# prototype1-ftdi-as-breakout.net
KiCad netlist of a schematic drawn in EAGLE
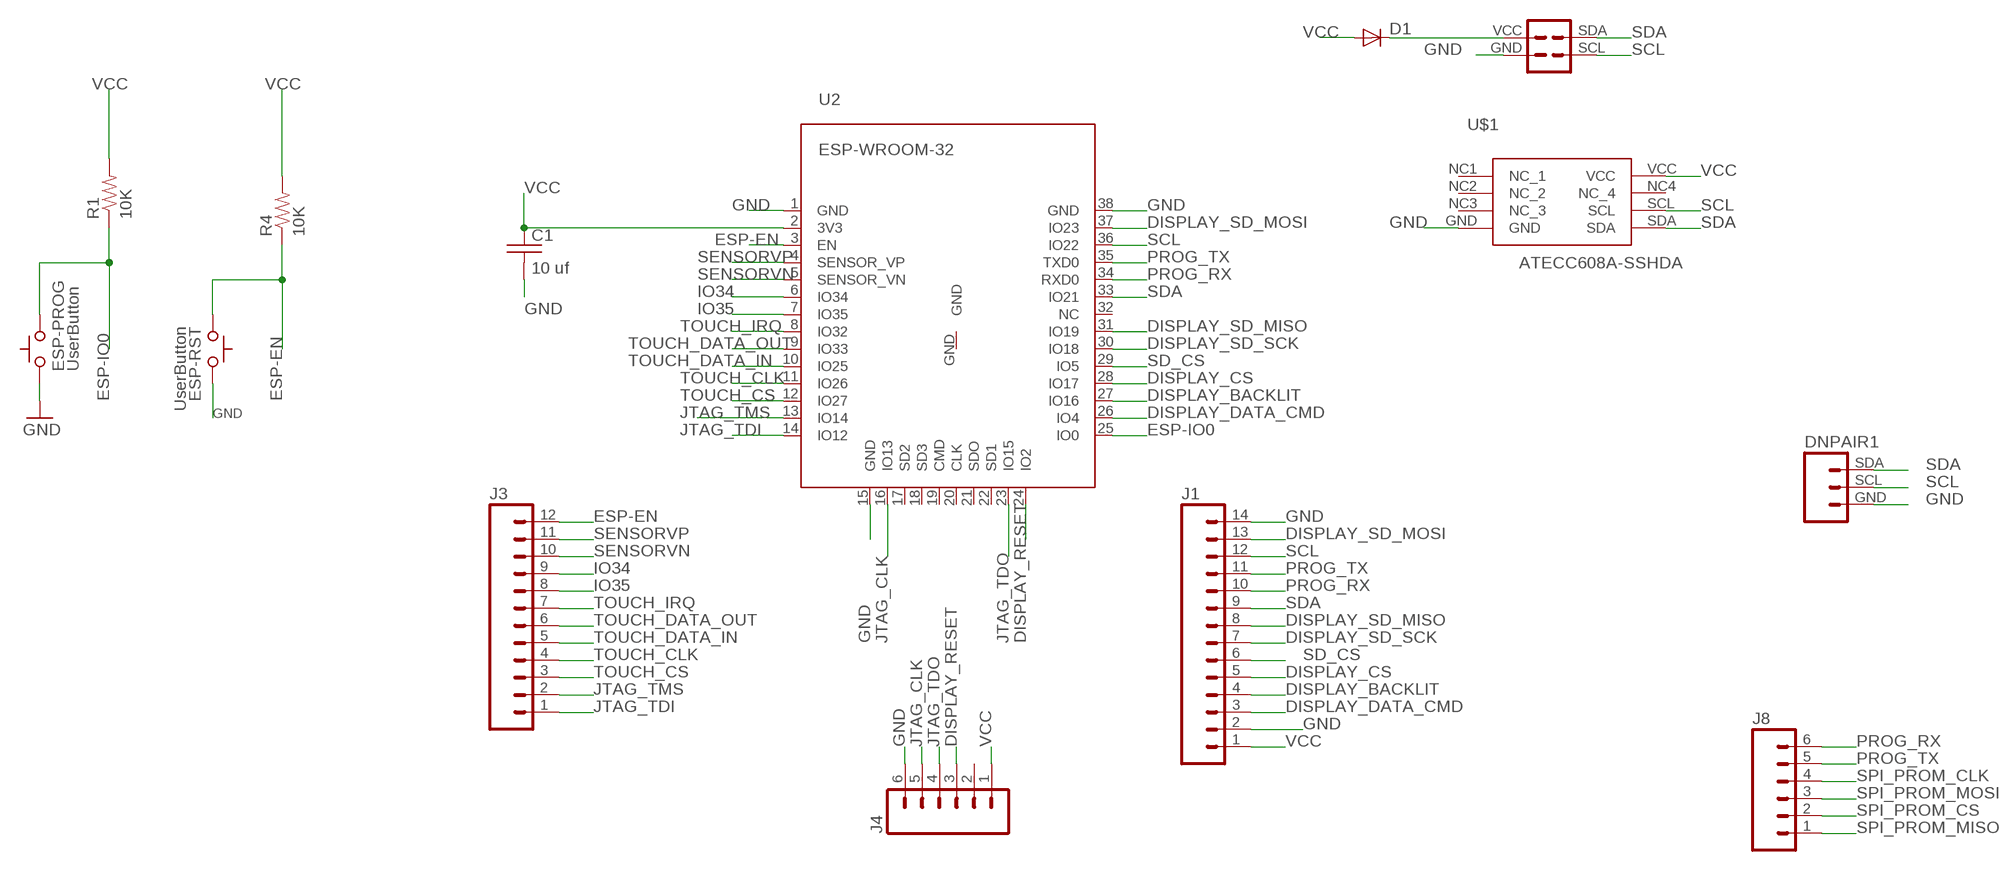
[diagram p0: schematic, sheet 1]
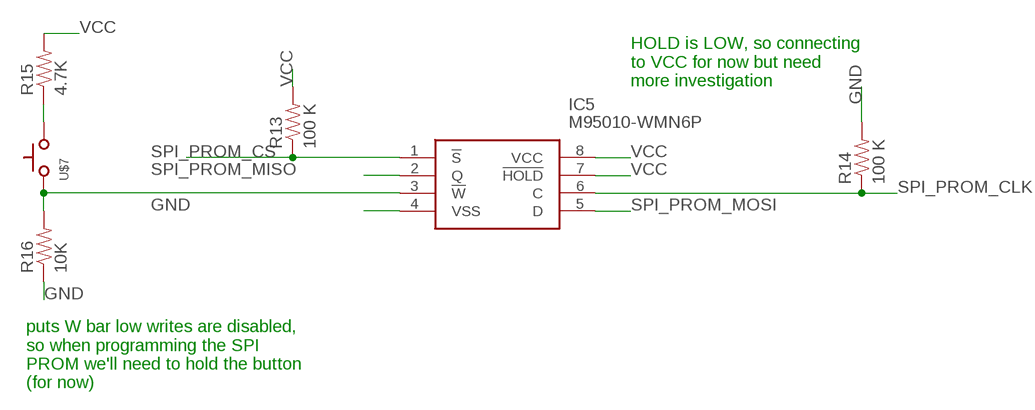
[diagram p1: schematic, sheet 2]
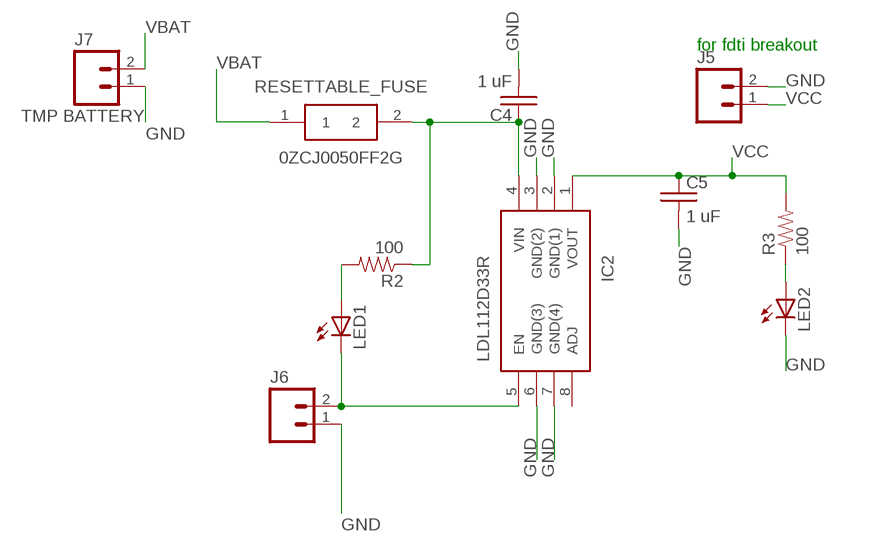
[diagram p2: schematic, sheet 3]
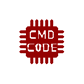
[diagram p3: schematic, sheet 4]

(export (version "E")
  (design (tool "Eeschema 10.0.6"))
  (components
    (comp (ref "IC5")
      (value "M95010-WMN6P")
      (footprint "eagle-import:SOIC127P600X175-8N")
      (fields
        (field (name "MOUSER_PART_NUMBER") "511-M95010-WMN6P")
        (field (name "RS_PART_NUMBER") "7147617")
      )
      (libsource (lib "eagle-import") (part "M95010-WMN6P"))
    )
    (comp (ref "R13")
      (value "100 K")
      (footprint "eagle-import:0805")
      (libsource (lib "eagle-import") (part "passives_RESISTOR0805-RES"))
    )
    (comp (ref "R14")
      (value "100 K")
      (footprint "eagle-import:0805")
      (libsource (lib "eagle-import") (part "passives_RESISTOR0805-RES"))
    )
    (comp (ref "R15")
      (value "4.7K")
      (footprint "eagle-import:0805")
      (libsource (lib "eagle-import") (part "passives_RESISTOR0805-RES"))
    )
    (comp (ref "R16")
      (value "10K")
      (footprint "eagle-import:0805")
      (libsource (lib "eagle-import") (part "passives_RESISTOR0805-RES"))
    )
    (comp (ref "U$7")
      (value "SWITCH_TACTILETACTILE-2PIN-NARROW")
      (footprint "eagle-import:TACTILE-2PIN-NARROW")
      (libsource (lib "eagle-import") (part "switches_SWITCH_TACTILETACTILE-2PIN-NARROW"))
    )
    (comp (ref "C4")
      (value "1 uF")
      (footprint "eagle-import:C0805")
      (libsource (lib "eagle-import") (part "C-USC0805"))
    )
    (comp (ref "C5")
      (value "1 uF")
      (footprint "eagle-import:C0805")
      (libsource (lib "eagle-import") (part "C-USC0805"))
    )
    (comp (ref "IC2")
      (value "LDL112D33R")
      (footprint "eagle-import:SOIC127P600X175-8N")
      (libsource (lib "eagle-import") (part "LDL112D33R"))
    )
    (comp (ref "J5")
      (value "M02PTH")
      (footprint "eagle-import:1X02")
      (libsource (lib "eagle-import") (part "M02PTH"))
    )
    (comp (ref "J6")
      (value "M02PTH")
      (footprint "eagle-import:1X02")
      (libsource (lib "eagle-import") (part "M02PTH"))
    )
    (comp (ref "J7")
      (value "TMP BATTERY")
      (footprint "eagle-import:1X02")
      (libsource (lib "eagle-import") (part "M02PTH"))
    )
    (comp (ref "LED1")
      (value "LED3MM")
      (footprint "eagle-import:LED3MM")
      (libsource (lib "eagle-import") (part "LED3MM"))
    )
    (comp (ref "LED2")
      (value "LED3MM")
      (footprint "eagle-import:LED3MM")
      (libsource (lib "eagle-import") (part "LED3MM"))
    )
    (comp (ref "R2")
      (value "100")
      (footprint "eagle-import:0805")
      (libsource (lib "eagle-import") (part "passives_RESISTOR0805-RES"))
    )
    (comp (ref "R3")
      (value "100")
      (footprint "eagle-import:0805")
      (libsource (lib "eagle-import") (part "passives_RESISTOR0805-RES"))
    )
    (comp (ref "RESETTABLE_FUSE")
      (value "0ZCJ0050FF2G")
      (footprint "eagle-import:FUSC3216X55N")
      (libsource (lib "eagle-import") (part "0ZCJ0050FF2G"))
    )
    (comp (ref "C1")
      (value "10 uf")
      (footprint "eagle-import:C0805")
      (libsource (lib "eagle-import") (part "C-USC0805"))
    )
    (comp (ref "D1")
      (value "DIODESMA")
      (footprint "eagle-import:SMA-DIODE")
      (libsource (lib "eagle-import") (part "DIODESMA"))
    )
    (comp (ref "DNPAIR1")
      (value "DARKNET_8_PAIR_CONNECTORPTH")
      (footprint "eagle-import:1X03")
      (libsource (lib "eagle-import") (part "DARKNET_8_PAIR_CONNECTORPTH"))
    )
    (comp (ref "ESP-PROG")
      (value "UserButton")
      (footprint "eagle-import:TACTILE-2PIN-NARROW")
      (libsource (lib "eagle-import") (part "SWITCH_TACTILETACTILE-2PIN-NARROW"))
    )
    (comp (ref "ESP-RST")
      (value "UserButton")
      (footprint "eagle-import:TACTILE-2PIN-NARROW")
      (libsource (lib "eagle-import") (part "SWITCH_TACTILETACTILE-2PIN-NARROW"))
    )
    (comp (ref "J1")
      (value "M14")
      (footprint "eagle-import:1X14")
      (libsource (lib "eagle-import") (part "M14"))
    )
    (comp (ref "J3")
      (value "M12PTH")
      (footprint "eagle-import:1X12")
      (libsource (lib "eagle-import") (part "M12PTH"))
    )
    (comp (ref "J4")
      (value "M06SILK_FEMALE_PTH")
      (footprint "eagle-import:1X06")
      (libsource (lib "eagle-import") (part "M06SILK_FEMALE_PTH"))
    )
    (comp (ref "J8")
      (value "M06SILK_FEMALE_PTH")
      (footprint "eagle-import:1X06")
      (libsource (lib "eagle-import") (part "M06SILK_FEMALE_PTH"))
    )
    (comp (ref "R1")
      (value "10K")
      (footprint "eagle-import:0805")
      (libsource (lib "eagle-import") (part "RESISTOR0805-RES"))
    )
    (comp (ref "R4")
      (value "10K")
      (footprint "eagle-import:0805")
      (libsource (lib "eagle-import") (part "RESISTOR0805-RES"))
    )
    (comp (ref "SHITTY_ADDON")
      (value "SAO1")
      (footprint "eagle-import:DC26SHITTY_ADDON_CONNECTOR")
      (libsource (lib "eagle-import") (part "DC26_SHITTY_ADDON_CONNECTORPTH"))
    )
    (comp (ref "U$1")
      (value "ATECC608A-SSHDA")
      (footprint "eagle-import:8-SOIC")
      (libsource (lib "eagle-import") (part "ATECC608A-SSHDA"))
    )
    (comp (ref "U2")
      (value "ESP-WROOM-32")
      (footprint "eagle-import:ESP-WROOM-32")
      (libsource (lib "eagle-import") (part "ESP-WROOM-32"))
    )
    (comp (ref "U$2")
      (value "CMD_C0DE_LOGOCMD_CODE_LOGO_TOP_COPPER")
      (footprint "eagle-import:CMD_C0DE_LOGO_TOP_COPPER")
      (libsource (lib "eagle-import") (part "CMD_C0DE_LOGOCMD_CODE_LOGO_TOP_COPPER"))
    )
  )
  (nets
    (net (code "1") (name "DISPLAY_BACKLIT") (class "Default")
      (node (ref "J1") (pin "4") (pinfunction "4_4") (pintype "passive"))
      (node (ref "U2") (pin "27") (pinfunction "IO16_27") (pintype "bidirectional"))
    )
    (net (code "2") (name "DISPLAY_CS") (class "Default")
      (node (ref "J1") (pin "5") (pinfunction "5_5") (pintype "passive"))
      (node (ref "U2") (pin "28") (pinfunction "IO17_28") (pintype "bidirectional"))
    )
    (net (code "3") (name "DISPLAY_DATA_CMD") (class "Default")
      (node (ref "J1") (pin "3") (pinfunction "3_3") (pintype "passive"))
      (node (ref "U2") (pin "26") (pinfunction "IO4_26") (pintype "bidirectional"))
    )
    (net (code "4") (name "DISPLAY_RESET") (class "Default")
      (node (ref "J4") (pin "3") (pinfunction "3_3") (pintype "passive"))
      (node (ref "U2") (pin "24") (pinfunction "IO2_24") (pintype "bidirectional"))
    )
    (net (code "5") (name "DISPLAY_SD_MISO") (class "Default")
      (node (ref "J1") (pin "8") (pinfunction "8_8") (pintype "passive"))
      (node (ref "U2") (pin "31") (pinfunction "IO19_31") (pintype "bidirectional"))
    )
    (net (code "6") (name "DISPLAY_SD_MOSI") (class "Default")
      (node (ref "J1") (pin "13") (pinfunction "13_13") (pintype "passive"))
      (node (ref "U2") (pin "37") (pinfunction "IO23_37") (pintype "bidirectional"))
    )
    (net (code "7") (name "DISPLAY_SD_SCK") (class "Default")
      (node (ref "J1") (pin "7") (pinfunction "7_7") (pintype "passive"))
      (node (ref "U2") (pin "30") (pinfunction "IO18_30") (pintype "bidirectional"))
    )
    (net (code "8") (name "ESP-EN") (class "Default")
      (node (ref "ESP-RST") (pin "P$2") (pinfunction "C_P$2") (pintype "passive"))
      (node (ref "J3") (pin "12") (pinfunction "12_12") (pintype "passive"))
      (node (ref "R4") (pin "1") (pinfunction "1_1") (pintype "passive"))
      (node (ref "U2") (pin "3") (pinfunction "EN_3") (pintype "bidirectional"))
    )
    (net (code "9") (name "ESP-IO0") (class "Default")
      (node (ref "ESP-PROG") (pin "P$1") (pinfunction "A_P$1") (pintype "passive"))
      (node (ref "R1") (pin "1") (pinfunction "1_1") (pintype "passive"))
      (node (ref "U2") (pin "25") (pinfunction "IO0_25") (pintype "bidirectional"))
    )
    (net (code "10") (name "GND") (class "Default")
      (node (ref "C1") (pin "2") (pinfunction "2_2") (pintype "passive"))
      (node (ref "C4") (pin "2") (pinfunction "2_2") (pintype "passive"))
      (node (ref "C5") (pin "2") (pinfunction "2_2") (pintype "passive"))
      (node (ref "DNPAIR1") (pin "GND") (pinfunction "GND_GND") (pintype "power_in"))
      (node (ref "ESP-PROG") (pin "P$2") (pinfunction "C_P$2") (pintype "passive"))
      (node (ref "ESP-RST") (pin "P$1") (pinfunction "A_P$1") (pintype "passive"))
      (node (ref "IC2") (pin "2") (pinfunction "GND(1)_2") (pintype "bidirectional"))
      (node (ref "IC2") (pin "3") (pinfunction "GND(2)_3") (pintype "bidirectional"))
      (node (ref "IC2") (pin "6") (pinfunction "GND(3)_6") (pintype "bidirectional"))
      (node (ref "IC2") (pin "7") (pinfunction "GND(4)_7") (pintype "bidirectional"))
      (node (ref "IC5") (pin "4") (pinfunction "VSS_4") (pintype "power_in"))
      (node (ref "J1") (pin "14") (pinfunction "14_14") (pintype "passive"))
      (node (ref "J1") (pin "2") (pinfunction "2_2") (pintype "passive"))
      (node (ref "J4") (pin "6") (pinfunction "6_6") (pintype "passive"))
      (node (ref "J5") (pin "2") (pinfunction "2_2") (pintype "passive"))
      (node (ref "J6") (pin "1") (pinfunction "1_1") (pintype "passive"))
      (node (ref "J7") (pin "1") (pinfunction "1_1") (pintype "passive"))
      (node (ref "LED2") (pin "K") (pinfunction "C_K") (pintype "output"))
      (node (ref "R14") (pin "2") (pinfunction "2_2") (pintype "passive"))
      (node (ref "R16") (pin "1") (pinfunction "1_1") (pintype "passive"))
      (node (ref "SHITTY_ADDON") (pin "GND") (pinfunction "GND_GND") (pintype "power_in"))
      (node (ref "U$1") (pin "GND") (pinfunction "GND_GND") (pintype "power_in"))
      (node (ref "U2") (pin "1") (pinfunction "GND_1") (pintype "bidirectional"))
      (node (ref "U2") (pin "15") (pinfunction "GND_15") (pintype "bidirectional"))
      (node (ref "U2") (pin "38") (pinfunction "GND_38") (pintype "bidirectional"))
    )
    (net (code "11") (name "IO34") (class "Default")
      (node (ref "J3") (pin "9") (pinfunction "9_9") (pintype "passive"))
      (node (ref "U2") (pin "6") (pinfunction "IO34_6") (pintype "bidirectional"))
    )
    (net (code "12") (name "IO35") (class "Default")
      (node (ref "J3") (pin "8") (pinfunction "8_8") (pintype "passive"))
      (node (ref "U2") (pin "7") (pinfunction "IO35_7") (pintype "bidirectional"))
    )
    (net (code "13") (name "JTAG_CLK") (class "Default")
      (node (ref "J4") (pin "5") (pinfunction "5_5") (pintype "passive"))
      (node (ref "U2") (pin "16") (pinfunction "IO13_16") (pintype "bidirectional"))
    )
    (net (code "14") (name "JTAG_TDI") (class "Default")
      (node (ref "J3") (pin "1") (pinfunction "1_1") (pintype "passive"))
      (node (ref "U2") (pin "14") (pinfunction "IO12_14") (pintype "bidirectional"))
    )
    (net (code "15") (name "JTAG_TDO") (class "Default")
      (node (ref "J4") (pin "4") (pinfunction "4_4") (pintype "passive"))
      (node (ref "U2") (pin "23") (pinfunction "IO15_23") (pintype "bidirectional"))
    )
    (net (code "16") (name "JTAG_TMS") (class "Default")
      (node (ref "J3") (pin "2") (pinfunction "2_2") (pintype "passive"))
      (node (ref "U2") (pin "13") (pinfunction "IO14_13") (pintype "bidirectional"))
    )
    (net (code "17") (name "Net-(D1-PadC)") (class "Default")
      (node (ref "D1") (pin "C") (pinfunction "C_C") (pintype "passive"))
      (node (ref "SHITTY_ADDON") (pin "VCC") (pinfunction "VCC_VCC") (pintype "power_in"))
    )
    (net (code "18") (name "Net-(IC2-EN)") (class "Default")
      (node (ref "IC2") (pin "5") (pinfunction "EN_5") (pintype "bidirectional"))
      (node (ref "J6") (pin "2") (pinfunction "2_2") (pintype "passive"))
      (node (ref "LED1") (pin "K") (pinfunction "C_K") (pintype "output"))
    )
    (net (code "19") (name "Net-(IC2-VIN)") (class "Default")
      (node (ref "C4") (pin "1") (pinfunction "1_1") (pintype "passive"))
      (node (ref "IC2") (pin "4") (pinfunction "VIN_4") (pintype "bidirectional"))
      (node (ref "R2") (pin "1") (pinfunction "1_1") (pintype "passive"))
      (node (ref "RESETTABLE_FUSE") (pin "2") (pinfunction "2_2") (pintype "passive"))
    )
    (net (code "20") (name "Net-(IC5-~{W})") (class "Default")
      (node (ref "IC5") (pin "3") (pinfunction "~{W}_3") (pintype "bidirectional"))
      (node (ref "R16") (pin "2") (pinfunction "2_2") (pintype "passive"))
      (node (ref "U$7") (pin "P$2") (pinfunction "C_P$2") (pintype "passive"))
    )
    (net (code "21") (name "Net-(LED1-PadA)") (class "Default")
      (node (ref "LED1") (pin "A") (pinfunction "A_A") (pintype "input"))
      (node (ref "R2") (pin "2") (pinfunction "2_2") (pintype "passive"))
    )
    (net (code "22") (name "Net-(LED2-PadA)") (class "Default")
      (node (ref "LED2") (pin "A") (pinfunction "A_A") (pintype "input"))
      (node (ref "R3") (pin "1") (pinfunction "1_1") (pintype "passive"))
    )
    (net (code "23") (name "Net-(U$7-A)") (class "Default")
      (node (ref "R15") (pin "1") (pinfunction "1_1") (pintype "passive"))
      (node (ref "U$7") (pin "P$1") (pinfunction "A_P$1") (pintype "passive"))
    )
    (net (code "24") (name "PROG_RX") (class "Default")
      (node (ref "J1") (pin "10") (pinfunction "10_10") (pintype "passive"))
      (node (ref "J8") (pin "6") (pinfunction "6_6") (pintype "passive"))
      (node (ref "U2") (pin "34") (pinfunction "RXD0_34") (pintype "bidirectional"))
    )
    (net (code "25") (name "PROG_TX") (class "Default")
      (node (ref "J1") (pin "11") (pinfunction "11_11") (pintype "passive"))
      (node (ref "J8") (pin "5") (pinfunction "5_5") (pintype "passive"))
      (node (ref "U2") (pin "35") (pinfunction "TXD0_35") (pintype "bidirectional"))
    )
    (net (code "26") (name "SCL") (class "Default")
      (node (ref "DNPAIR1") (pin "SCL") (pinfunction "SCL_SCL") (pintype "bidirectional"))
      (node (ref "J1") (pin "12") (pinfunction "12_12") (pintype "passive"))
      (node (ref "SHITTY_ADDON") (pin "SCL") (pinfunction "SCL_SCL") (pintype "bidirectional"))
      (node (ref "U$1") (pin "SCL") (pinfunction "SCL_SCL") (pintype "bidirectional"))
      (node (ref "U2") (pin "36") (pinfunction "IO22_36") (pintype "bidirectional"))
    )
    (net (code "27") (name "SDA") (class "Default")
      (node (ref "DNPAIR1") (pin "SDA") (pinfunction "SDA_SDA") (pintype "bidirectional"))
      (node (ref "J1") (pin "9") (pinfunction "9_9") (pintype "passive"))
      (node (ref "SHITTY_ADDON") (pin "SDA") (pinfunction "SDA_SDA") (pintype "bidirectional"))
      (node (ref "U$1") (pin "SDA") (pinfunction "SDA_SDA") (pintype "bidirectional"))
      (node (ref "U2") (pin "33") (pinfunction "IO21_33") (pintype "bidirectional"))
    )
    (net (code "28") (name "SD_CS") (class "Default")
      (node (ref "J1") (pin "6") (pinfunction "6_6") (pintype "passive"))
      (node (ref "U2") (pin "29") (pinfunction "IO5_29") (pintype "bidirectional"))
    )
    (net (code "29") (name "SENSORVN") (class "Default")
      (node (ref "J3") (pin "10") (pinfunction "10_10") (pintype "passive"))
      (node (ref "U2") (pin "5") (pinfunction "SENSOR_VN_5") (pintype "bidirectional"))
    )
    (net (code "30") (name "SENSORVP") (class "Default")
      (node (ref "J3") (pin "11") (pinfunction "11_11") (pintype "passive"))
      (node (ref "U2") (pin "4") (pinfunction "SENSOR_VP_4") (pintype "bidirectional"))
    )
    (net (code "31") (name "SPI_PROM_CLK") (class "Default")
      (node (ref "IC5") (pin "6") (pinfunction "C_6") (pintype "bidirectional"))
      (node (ref "J8") (pin "4") (pinfunction "4_4") (pintype "passive"))
      (node (ref "R14") (pin "1") (pinfunction "1_1") (pintype "passive"))
    )
    (net (code "32") (name "SPI_PROM_CS") (class "Default")
      (node (ref "IC5") (pin "1") (pinfunction "~{S}_1") (pintype "bidirectional"))
      (node (ref "J8") (pin "2") (pinfunction "2_2") (pintype "passive"))
      (node (ref "R13") (pin "1") (pinfunction "1_1") (pintype "passive"))
    )
    (net (code "33") (name "SPI_PROM_MISO") (class "Default")
      (node (ref "IC5") (pin "2") (pinfunction "Q_2") (pintype "output"))
      (node (ref "J8") (pin "1") (pinfunction "1_1") (pintype "passive"))
    )
    (net (code "34") (name "SPI_PROM_MOSI") (class "Default")
      (node (ref "IC5") (pin "5") (pinfunction "D_5") (pintype "input"))
      (node (ref "J8") (pin "3") (pinfunction "3_3") (pintype "passive"))
    )
    (net (code "35") (name "TOUCH_CLK") (class "Default")
      (node (ref "J3") (pin "4") (pinfunction "4_4") (pintype "passive"))
      (node (ref "U2") (pin "11") (pinfunction "IO26_11") (pintype "bidirectional"))
    )
    (net (code "36") (name "TOUCH_CS") (class "Default")
      (node (ref "J3") (pin "3") (pinfunction "3_3") (pintype "passive"))
      (node (ref "U2") (pin "12") (pinfunction "IO27_12") (pintype "bidirectional"))
    )
    (net (code "37") (name "TOUCH_DATA_IN") (class "Default")
      (node (ref "J3") (pin "5") (pinfunction "5_5") (pintype "passive"))
      (node (ref "U2") (pin "10") (pinfunction "IO25_10") (pintype "bidirectional"))
    )
    (net (code "38") (name "TOUCH_DATA_OUT") (class "Default")
      (node (ref "J3") (pin "6") (pinfunction "6_6") (pintype "passive"))
      (node (ref "U2") (pin "9") (pinfunction "IO33_9") (pintype "bidirectional"))
    )
    (net (code "39") (name "TOUCH_IRQ") (class "Default")
      (node (ref "J3") (pin "7") (pinfunction "7_7") (pintype "passive"))
      (node (ref "U2") (pin "8") (pinfunction "IO32_8") (pintype "bidirectional"))
    )
    (net (code "40") (name "VBAT") (class "Default")
      (node (ref "J7") (pin "2") (pinfunction "2_2") (pintype "passive"))
      (node (ref "RESETTABLE_FUSE") (pin "1") (pinfunction "1_1") (pintype "passive"))
    )
    (net (code "41") (name "VCC") (class "Default")
      (node (ref "C1") (pin "1") (pinfunction "1_1") (pintype "passive"))
      (node (ref "C5") (pin "1") (pinfunction "1_1") (pintype "passive"))
      (node (ref "D1") (pin "A") (pinfunction "A_A") (pintype "passive"))
      (node (ref "IC2") (pin "1") (pinfunction "VOUT_1") (pintype "bidirectional"))
      (node (ref "IC5") (pin "7") (pinfunction "~{HOLD}_7") (pintype "bidirectional"))
      (node (ref "IC5") (pin "8") (pinfunction "VCC_8") (pintype "power_in"))
      (node (ref "J1") (pin "1") (pinfunction "1_1") (pintype "passive"))
      (node (ref "J4") (pin "1") (pinfunction "1_1") (pintype "passive"))
      (node (ref "J5") (pin "1") (pinfunction "1_1") (pintype "passive"))
      (node (ref "R1") (pin "2") (pinfunction "2_2") (pintype "passive"))
      (node (ref "R13") (pin "2") (pinfunction "2_2") (pintype "passive"))
      (node (ref "R15") (pin "2") (pinfunction "2_2") (pintype "passive"))
      (node (ref "R3") (pin "2") (pinfunction "2_2") (pintype "passive"))
      (node (ref "R4") (pin "2") (pinfunction "2_2") (pintype "passive"))
      (node (ref "U$1") (pin "VCC") (pinfunction "VCC_VCC") (pintype "power_in"))
      (node (ref "U2") (pin "2") (pinfunction "3V3_2") (pintype "bidirectional"))
    )
    (net (code "42") (name "unconnected-(IC2-ADJ-Pad8)") (class "Default")
      (node (ref "IC2") (pin "8") (pinfunction "ADJ_8") (pintype "bidirectional"))
    )
    (net (code "43") (name "unconnected-(J4-Pad2)") (class "Default")
      (node (ref "J4") (pin "2") (pinfunction "2_2") (pintype "passive"))
    )
    (net (code "44") (name "unconnected-(U$1-NC_1-PadNC1)") (class "Default")
      (node (ref "U$1") (pin "NC1") (pinfunction "NC_1_NC1") (pintype "no_connect"))
    )
    (net (code "45") (name "unconnected-(U$1-NC_2-PadNC2)") (class "Default")
      (node (ref "U$1") (pin "NC2") (pinfunction "NC_2_NC2") (pintype "no_connect"))
    )
    (net (code "46") (name "unconnected-(U$1-NC_3-PadNC3)") (class "Default")
      (node (ref "U$1") (pin "NC3") (pinfunction "NC_3_NC3") (pintype "no_connect"))
    )
    (net (code "47") (name "unconnected-(U$1-NC_4-PadNC4)") (class "Default")
      (node (ref "U$1") (pin "NC4") (pinfunction "NC_4_NC4") (pintype "no_connect"))
    )
    (net (code "48") (name "unconnected-(U2-CLK-Pad20)") (class "Default")
      (node (ref "U2") (pin "20") (pinfunction "CLK_20") (pintype "bidirectional"))
    )
    (net (code "49") (name "unconnected-(U2-CMD-Pad19)") (class "Default")
      (node (ref "U2") (pin "19") (pinfunction "CMD_19") (pintype "bidirectional"))
    )
    (net (code "50") (name "unconnected-(U2-NC-Pad32)") (class "Default")
      (node (ref "U2") (pin "32") (pinfunction "NC_32") (pintype "bidirectional"))
    )
    (net (code "51") (name "unconnected-(U2-PadGND)") (class "Default")
      (node (ref "U2") (pin "GND") (pinfunction "GND_GND") (pintype "bidirectional"))
    )
    (net (code "52") (name "unconnected-(U2-SD1-Pad22)") (class "Default")
      (node (ref "U2") (pin "22") (pinfunction "SD1_22") (pintype "bidirectional"))
    )
    (net (code "53") (name "unconnected-(U2-SD2-Pad17)") (class "Default")
      (node (ref "U2") (pin "17") (pinfunction "SD2_17") (pintype "bidirectional"))
    )
    (net (code "54") (name "unconnected-(U2-SD3-Pad18)") (class "Default")
      (node (ref "U2") (pin "18") (pinfunction "SD3_18") (pintype "bidirectional"))
    )
    (net (code "55") (name "unconnected-(U2-SDO-Pad21)") (class "Default")
      (node (ref "U2") (pin "21") (pinfunction "SDO_21") (pintype "bidirectional"))
    )
  )
)
